# rf_smps.net
KiCad netlist of a schematic drawn in Altium Designer
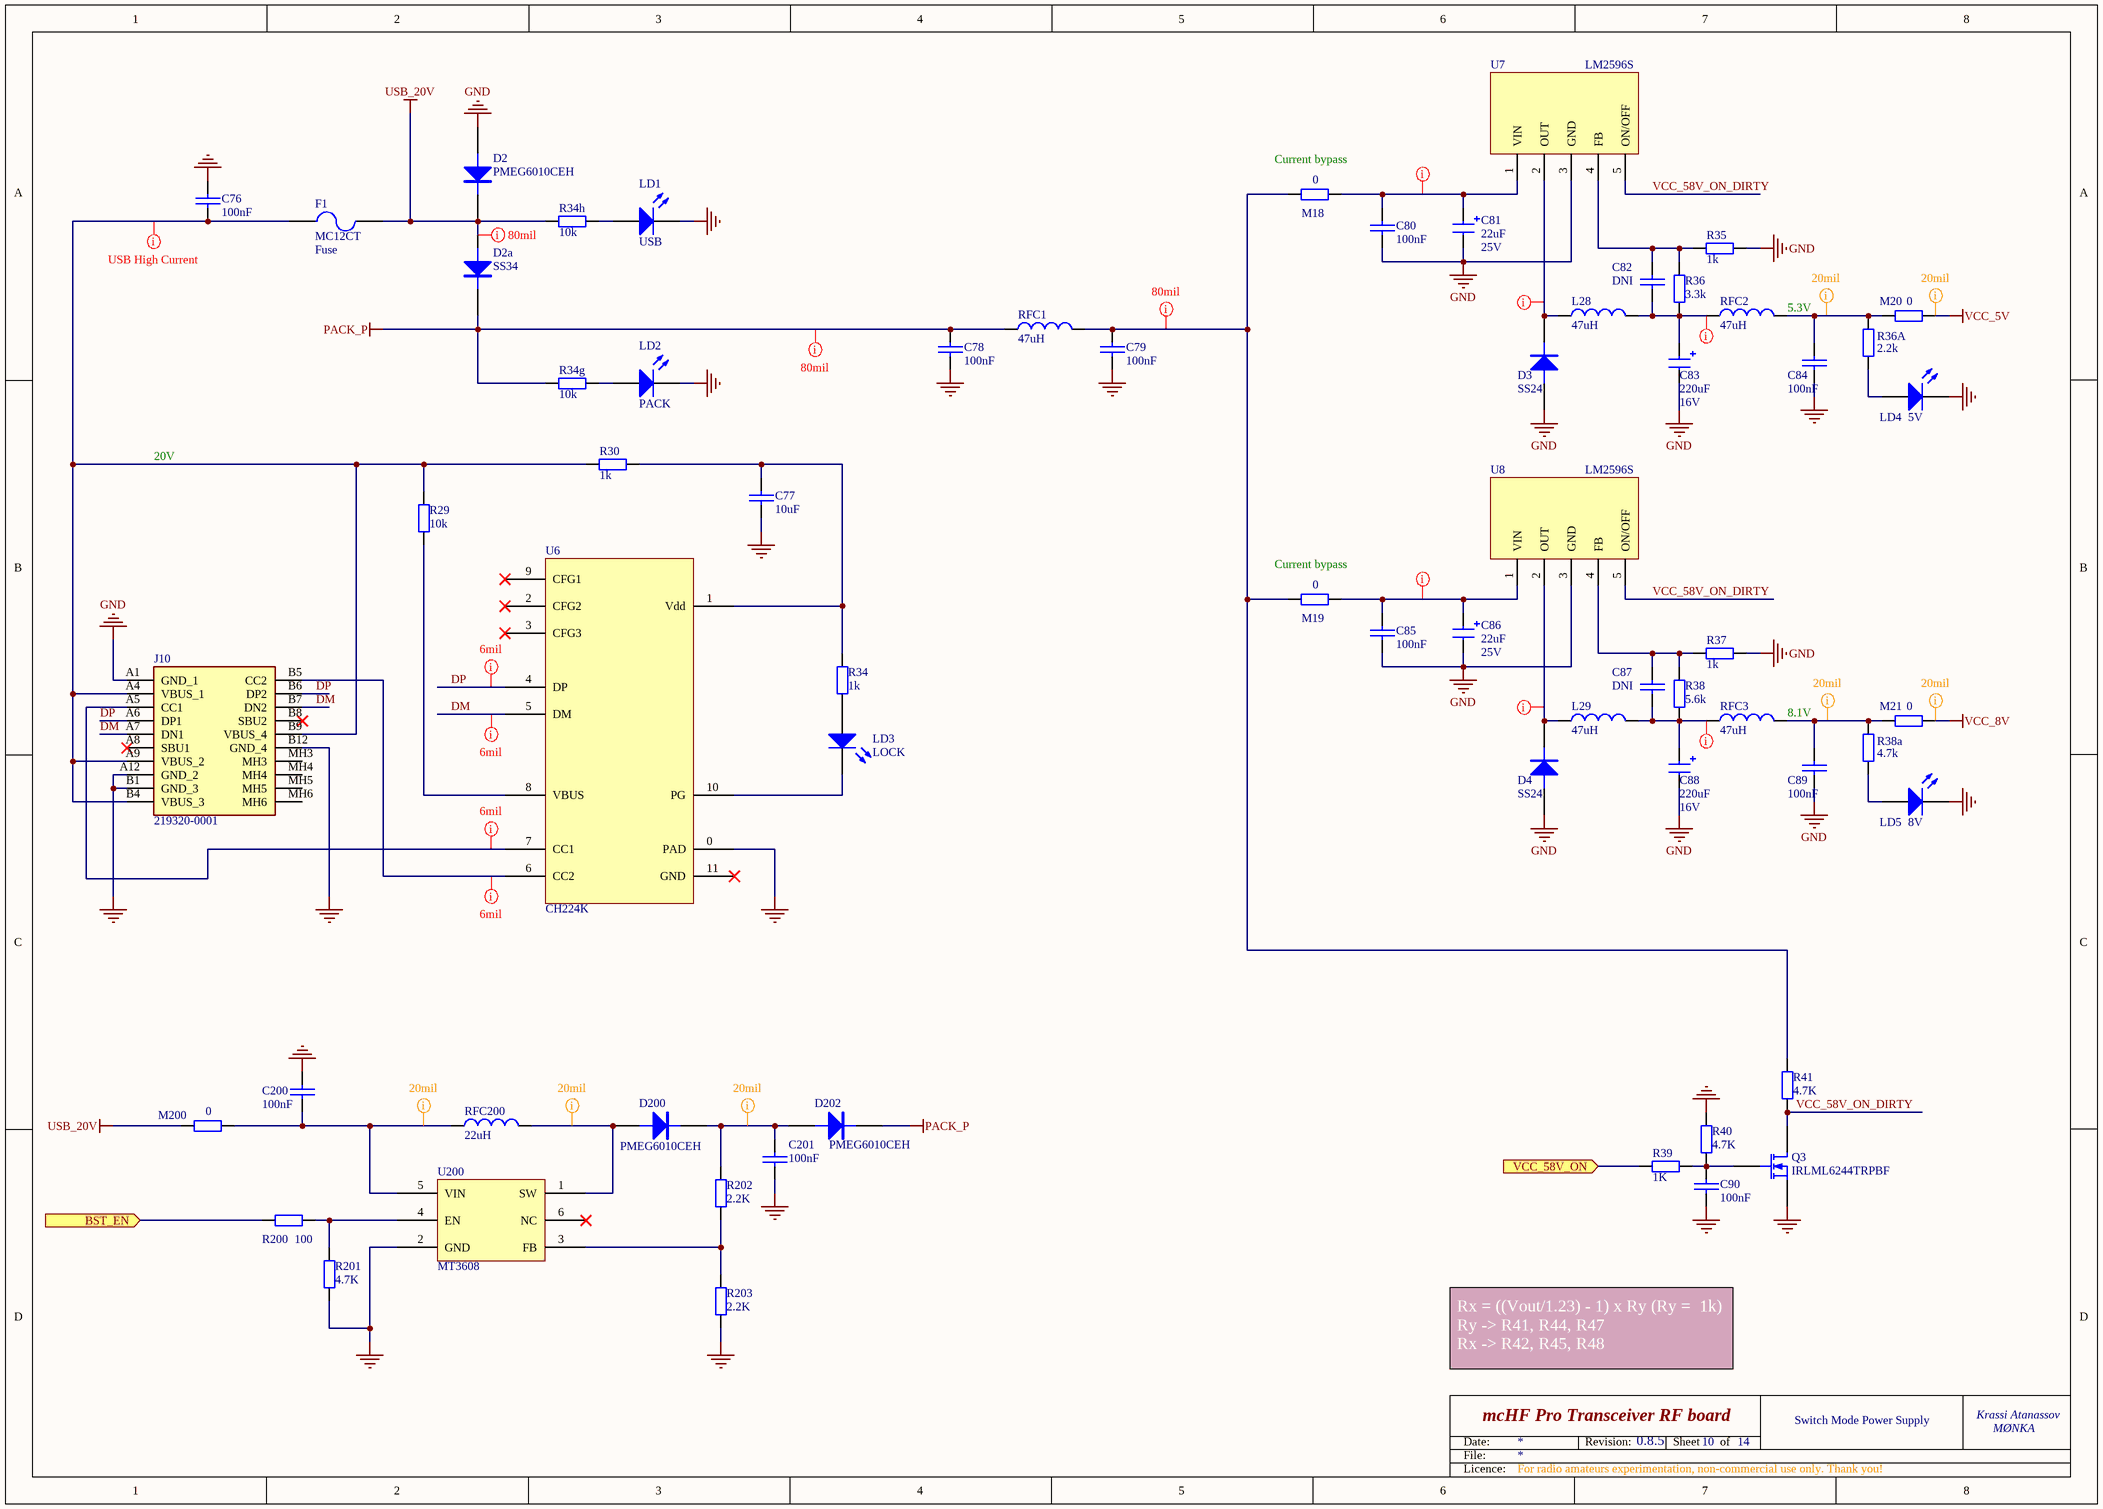
[diagram p0: rf_smps.SchDoc]

(export (version "E")
  (design (tool "Eeschema 10.0.6"))
  (components
    (comp (ref "C76")
      (value "100nF")
      (footprint "0805")
      (description "Capacitor")
      (libsource (lib "mcHF_rf") (part "CAP"))
    )
    (comp (ref "C77")
      (value "10uF")
      (footprint "0805")
      (description "Capacitor")
      (libsource (lib "mcHF_rf") (part "CAP"))
    )
    (comp (ref "C78")
      (value "100nF")
      (footprint "0805")
      (description "Capacitor")
      (fields (field (name "VOLTAGE") "100V"))
      (libsource (lib "mcHF_rf") (part "CAP"))
    )
    (comp (ref "C79")
      (value "100nF")
      (footprint "0805")
      (description "Capacitor")
      (fields (field (name "VOLTAGE") "100V"))
      (libsource (lib "mcHF_rf") (part "CAP"))
    )
    (comp (ref "C80")
      (value "100nF")
      (footprint "0805")
      (description "Capacitor")
      (fields (field (name "VOLTAGE") "100V"))
      (libsource (lib "mcHF_rf") (part "CAP"))
    )
    (comp (ref "C81")
      (value "22uF")
      (footprint "1206_Elec_Cap")
      (description "Electrolitic capacitor")
      (fields (field (name "VOLTAGE") "25V"))
      (libsource (lib "mcHF_rf") (part "CAP-POL"))
    )
    (comp (ref "C82")
      (value "DNI")
      (footprint "0805")
      (description "Capacitor")
      (fields (field (name "VOLTAGE") "100V"))
      (libsource (lib "mcHF_rf") (part "CAP"))
    )
    (comp (ref "C83")
      (value "220uF")
      (footprint "CAP_ALUM_Pro")
      (description "Electrolitic capacitor")
      (fields (field (name "VOLTAGE") "16V"))
      (libsource (lib "mcHF_rf") (part "CAP-POL"))
    )
    (comp (ref "C84")
      (value "100nF")
      (footprint "0805")
      (description "Capacitor")
      (fields (field (name "VOLTAGE") "100V"))
      (libsource (lib "mcHF_rf") (part "CAP"))
    )
    (comp (ref "C85")
      (value "100nF")
      (footprint "0805")
      (description "Capacitor")
      (fields (field (name "VOLTAGE") "100V"))
      (libsource (lib "mcHF_rf") (part "CAP"))
    )
    (comp (ref "C86")
      (value "22uF")
      (footprint "1206_Elec_Cap")
      (description "Electrolitic capacitor")
      (fields (field (name "VOLTAGE") "25V"))
      (libsource (lib "mcHF_rf") (part "CAP-POL"))
    )
    (comp (ref "C87")
      (value "DNI")
      (footprint "0805")
      (description "Capacitor")
      (fields (field (name "VOLTAGE") "100V"))
      (libsource (lib "mcHF_rf") (part "CAP"))
    )
    (comp (ref "C88")
      (value "220uF")
      (footprint "CAP_ALUM_Pro")
      (description "Electrolitic capacitor")
      (fields (field (name "VOLTAGE") "16V"))
      (libsource (lib "mcHF_rf") (part "CAP-POL"))
    )
    (comp (ref "C89")
      (value "100nF")
      (footprint "0805")
      (description "Capacitor")
      (fields (field (name "VOLTAGE") "100V"))
      (libsource (lib "mcHF_rf") (part "CAP"))
    )
    (comp (ref "C90")
      (value "100nF")
      (footprint "0805")
      (description "Capacitor")
      (fields (field (name "VOLTAGE") "100V"))
      (libsource (lib "mcHF_rf") (part "CAP"))
    )
    (comp (ref "C200")
      (value "100nF")
      (footprint "0805")
      (description "Capacitor")
      (libsource (lib "mcHF_ui") (part "CAP"))
    )
    (comp (ref "C201")
      (value "100nF")
      (footprint "0805")
      (description "Capacitor")
      (libsource (lib "mcHF_ui") (part "CAP"))
    )
    (comp (ref "D2")
      (value "PMEG6010CEH")
      (footprint "SOD87")
      (description "DIODE, SCHOTTKY, 1A, 60V, SOD-123F")
      (libsource (lib "mcHF_rf") (part "PMEG6010CEH"))
    )
    (comp (ref "D2a")
      (value "SS34")
      (footprint "DO214")
      (description "DIODE, SCHOTTKY, 1A, 60V, SOD-123F")
      (libsource (lib "mcHF_rf") (part "PMEG6010CEH"))
    )
    (comp (ref "D3")
      (value "SS24")
      (footprint "DO214")
      (description "DIODE, SCHOTTKY, 1A, 60V, SOD-123F")
      (libsource (lib "mcHF_rf") (part "PMEG6010CEH"))
    )
    (comp (ref "D4")
      (value "SS24")
      (footprint "DO214")
      (description "DIODE, SCHOTTKY, 1A, 60V, SOD-123F")
      (libsource (lib "mcHF_rf") (part "PMEG6010CEH"))
    )
    (comp (ref "D200")
      (value "PMEG6010CEH")
      (footprint "SOD87")
      (description "DIODE, SCHOTTKY, 1A, 60V, SOD-123F")
      (libsource (lib "mcHF_rf") (part "PMEG6010CEH"))
    )
    (comp (ref "D202")
      (value "PMEG6010CEH")
      (footprint "SOD87")
      (description "DIODE, SCHOTTKY, 1A, 60V, SOD-123F")
      (libsource (lib "mcHF_rf") (part "PMEG6010CEH"))
    )
    (comp (ref "F1")
      (value "MC12CT")
      (footprint "1206")
      (description "Fuse")
      (fields (field (name "FUNCTION") "Fuse"))
      (libsource (lib "mcHF_rf") (part "Fuse"))
    )
    (comp (ref "J10")
      (value "219320-0001")
      (footprint "MOLX_USB")
      (fields (field (name "MOUSER PART NUMBER") "538-219320-0001"))
      (libsource (lib "__rf") (part "219320-0001"))
    )
    (comp (ref "L28")
      (value "47uH")
      (footprint "CD75")
      (description "POWER INDUCTOR, 47UH, 1210")
      (libsource (lib "mcHF_rf") (part "TDK-NLV25T"))
    )
    (comp (ref "L29")
      (value "47uH")
      (footprint "CD75")
      (description "POWER INDUCTOR, 47UH, 1210")
      (libsource (lib "mcHF_rf") (part "TDK-NLV25T"))
    )
    (comp (ref "LD1")
      (value "USB")
      (footprint "1206_Elec_Cap")
      (description "LED 3mm")
      (libsource (lib "mcHF_ui") (part "LED2"))
    )
    (comp (ref "LD2")
      (value "PACK")
      (footprint "1206_Elec_Cap")
      (description "LED 3mm")
      (libsource (lib "mcHF_ui") (part "LED2"))
    )
    (comp (ref "LD3")
      (value "LOCK")
      (footprint "1206_Elec_Cap")
      (description "LED 3mm")
      (libsource (lib "mcHF_ui") (part "LED2"))
    )
    (comp (ref "LD4")
      (value "5V")
      (footprint "1206_Elec_Cap")
      (description "LED 3mm")
      (libsource (lib "mcHF_ui") (part "LED2"))
    )
    (comp (ref "LD5")
      (value "8V")
      (footprint "1206_Elec_Cap")
      (description "LED 3mm")
      (libsource (lib "mcHF_ui") (part "LED2"))
    )
    (comp (ref "M18")
      (value "0")
      (footprint "0805")
      (description "Resistor")
      (libsource (lib "") (part "RES_1"))
    )
    (comp (ref "M19")
      (value "0")
      (footprint "0805")
      (description "Resistor")
      (libsource (lib "") (part "RES_1"))
    )
    (comp (ref "M20")
      (value "0")
      (footprint "0805")
      (description "Resistor")
      (libsource (lib "") (part "RES_1"))
    )
    (comp (ref "M21")
      (value "0")
      (footprint "0805")
      (description "Resistor")
      (libsource (lib "") (part "RES_1"))
    )
    (comp (ref "M200")
      (value "0")
      (footprint "0805")
      (description "Resistor")
      (libsource (lib "") (part "RES_1"))
    )
    (comp (ref "Q3")
      (value "IRLML6244TRPBF")
      (footprint "SOT-23-Pro")
      (description "N-Channel MOSFET")
      (libsource (lib "mcHF_ui_b") (part "MOSFET-N"))
    )
    (comp (ref "R29")
      (value "10k")
      (footprint "0805")
      (description "Resistor")
      (libsource (lib "mcHF_rf") (part "RES"))
    )
    (comp (ref "R30")
      (value "1k")
      (footprint "0805")
      (description "Resistor")
      (libsource (lib "") (part "RES_2"))
    )
    (comp (ref "R34")
      (value "1k")
      (footprint "0805")
      (description "Resistor")
      (libsource (lib "mcHF_rf") (part "RES"))
    )
    (comp (ref "R34g")
      (value "10k")
      (footprint "0805")
      (description "Resistor")
      (libsource (lib "") (part "RES_1"))
    )
    (comp (ref "R34h")
      (value "10k")
      (footprint "0805")
      (description "Resistor")
      (libsource (lib "") (part "RES_1"))
    )
    (comp (ref "R35")
      (value "1k")
      (footprint "0805")
      (description "Resistor")
      (libsource (lib "") (part "RES_2"))
    )
    (comp (ref "R36")
      (value "3.3k")
      (footprint "0805")
      (description "Resistor")
      (libsource (lib "mcHF_rf") (part "RES"))
    )
    (comp (ref "R36A")
      (value "2.2k")
      (footprint "0805")
      (description "Resistor")
      (libsource (lib "mcHF_rf") (part "RES"))
    )
    (comp (ref "R37")
      (value "1k")
      (footprint "0805")
      (description "Resistor")
      (libsource (lib "") (part "RES_2"))
    )
    (comp (ref "R38")
      (value "5.6k")
      (footprint "0805")
      (description "Resistor")
      (libsource (lib "mcHF_rf") (part "RES"))
    )
    (comp (ref "R38a")
      (value "4.7k")
      (footprint "0805")
      (description "Resistor")
      (libsource (lib "mcHF_rf") (part "RES"))
    )
    (comp (ref "R39")
      (value "1K")
      (footprint "0805")
      (description "Resistor")
      (libsource (lib "") (part "RES_2"))
    )
    (comp (ref "R40")
      (value "4.7K")
      (footprint "0805")
      (description "Resistor")
      (libsource (lib "mcHF_rf") (part "RES"))
    )
    (comp (ref "R41")
      (value "4.7K")
      (footprint "0805")
      (description "Resistor")
      (libsource (lib "mcHF_rf") (part "RES"))
    )
    (comp (ref "R200")
      (value "100")
      (footprint "0805")
      (description "Resistor")
      (libsource (lib "") (part "RES_2"))
    )
    (comp (ref "R201")
      (value "4.7K")
      (footprint "0805")
      (description "Resistor")
      (libsource (lib "") (part "RES_1"))
    )
    (comp (ref "R202")
      (value "2.2K")
      (footprint "0805")
      (description "Resistor")
      (libsource (lib "mcHF_ui") (part "RES"))
    )
    (comp (ref "R203")
      (value "2.2K")
      (footprint "0805")
      (description "Resistor")
      (libsource (lib "mcHF_ui") (part "RES"))
    )
    (comp (ref "RFC1")
      (value "47uH")
      (footprint "BIG_IND")
      (description "POWER INDUCTOR, 47UH, 1210")
      (libsource (lib "mcHF_rf") (part "TDK-NLV25T"))
    )
    (comp (ref "RFC2")
      (value "47uH")
      (footprint "CD75")
      (description "POWER INDUCTOR, 47UH, 1210")
      (libsource (lib "mcHF_rf") (part "TDK-NLV25T"))
    )
    (comp (ref "RFC3")
      (value "47uH")
      (footprint "CD75")
      (description "POWER INDUCTOR, 47UH, 1210")
      (libsource (lib "mcHF_rf") (part "TDK-NLV25T"))
    )
    (comp (ref "RFC200")
      (value "22uH")
      (footprint "0805")
      (description "Power Inductor")
      (libsource (lib "mcHF_ui") (part "Inductor"))
    )
    (comp (ref "U6")
      (value "CH224K")
      (footprint "ch224k")
      (description "USB-PD trigger chip")
      (libsource (lib "__rf") (part "CH224K"))
    )
    (comp (ref "U7")
      (value "LM2596S")
      (footprint "TO-263-5")
      (description "V REG ADJ +5/20V, SMPS TO-263-5")
      (libsource (lib "mcHF_rf") (part "LM2596S"))
    )
    (comp (ref "U8")
      (value "LM2596S")
      (footprint "TO-263-5")
      (description "V REG ADJ +5/20V, SMPS TO-263-5")
      (libsource (lib "mcHF_rf") (part "LM2596S"))
    )
    (comp (ref "U200")
      (value "MT3608")
      (footprint "SOT25-6")
      (description "Charge Pump")
      (libsource (lib "__rf") (part "MT3608"))
    )
  )
  (nets
    (net (code "1") (name "/BST_EN") (class "Default")
      (node (ref "R200") (pin "1") (pinfunction "1_1") (pintype "passive"))
    )
    (net (code "2") (name "/DM") (class "Default")
      (node (ref "J10") (pin "A7") (pinfunction "DN1_A7") (pintype "passive"))
      (node (ref "J10") (pin "B7") (pinfunction "DN2_B7") (pintype "passive"))
      (node (ref "U6") (pin "5") (pinfunction "DM_5") (pintype "passive"))
    )
    (net (code "3") (name "/DP") (class "Default")
      (node (ref "J10") (pin "A6") (pinfunction "DP1_A6") (pintype "passive"))
      (node (ref "J10") (pin "B6") (pinfunction "DP2_B6") (pintype "passive"))
      (node (ref "U6") (pin "4") (pinfunction "DP_4") (pintype "passive"))
    )
    (net (code "4") (name "/VCC_58V_ON") (class "Default")
      (node (ref "R39") (pin "1") (pinfunction "1_1") (pintype "passive"))
    )
    (net (code "5") (name "/VCC_58V_ON_DIRTY") (class "Default")
      (node (ref "Q3") (pin "3") (pinfunction "D_3") (pintype "passive"))
      (node (ref "R41") (pin "1") (pinfunction "1_1") (pintype "passive"))
      (node (ref "U7") (pin "5") (pinfunction "ON/OFF_5") (pintype "passive"))
      (node (ref "U8") (pin "5") (pinfunction "ON/OFF_5") (pintype "passive"))
    )
    (net (code "6") (name "GND") (class "Default")
      (node (ref "C200") (pin "1") (pinfunction "1_1") (pintype "passive"))
      (node (ref "C201") (pin "2") (pinfunction "2_2") (pintype "passive"))
      (node (ref "C76") (pin "1") (pinfunction "1_1") (pintype "passive"))
      (node (ref "C77") (pin "2") (pinfunction "2_2") (pintype "passive"))
      (node (ref "C78") (pin "1") (pinfunction "1_1") (pintype "passive"))
      (node (ref "C79") (pin "1") (pinfunction "1_1") (pintype "passive"))
      (node (ref "C80") (pin "2") (pinfunction "2_2") (pintype "passive"))
      (node (ref "C81") (pin "2") (pinfunction "2_2") (pintype "passive"))
      (node (ref "C83") (pin "2") (pinfunction "2_2") (pintype "passive"))
      (node (ref "C84") (pin "2") (pinfunction "2_2") (pintype "passive"))
      (node (ref "C85") (pin "2") (pinfunction "2_2") (pintype "passive"))
      (node (ref "C86") (pin "2") (pinfunction "2_2") (pintype "passive"))
      (node (ref "C88") (pin "2") (pinfunction "2_2") (pintype "passive"))
      (node (ref "C89") (pin "2") (pinfunction "2_2") (pintype "passive"))
      (node (ref "C90") (pin "2") (pinfunction "2_2") (pintype "passive"))
      (node (ref "D2") (pin "1") (pinfunction "A_1") (pintype "passive"))
      (node (ref "D3") (pin "1") (pinfunction "A_1") (pintype "passive"))
      (node (ref "D4") (pin "1") (pinfunction "A_1") (pintype "passive"))
      (node (ref "J10") (pin "A1") (pinfunction "GND_1_A1") (pintype "passive"))
      (node (ref "J10") (pin "A12") (pinfunction "GND_2_A12") (pintype "passive"))
      (node (ref "J10") (pin "B1") (pinfunction "GND_3_B1") (pintype "passive"))
      (node (ref "J10") (pin "B12") (pinfunction "GND_4_B12") (pintype "passive"))
      (node (ref "LD1") (pin "2") (pinfunction "K_2") (pintype "passive"))
      (node (ref "LD2") (pin "2") (pinfunction "K_2") (pintype "passive"))
      (node (ref "LD4") (pin "2") (pinfunction "K_2") (pintype "passive"))
      (node (ref "LD5") (pin "2") (pinfunction "K_2") (pintype "passive"))
      (node (ref "Q3") (pin "2") (pinfunction "S_2") (pintype "passive"))
      (node (ref "R201") (pin "1") (pinfunction "1_1") (pintype "passive"))
      (node (ref "R203") (pin "2") (pinfunction "2_2") (pintype "passive"))
      (node (ref "R35") (pin "2") (pinfunction "2_2") (pintype "passive"))
      (node (ref "R37") (pin "2") (pinfunction "2_2") (pintype "passive"))
      (node (ref "R40") (pin "2") (pinfunction "2_2") (pintype "passive"))
      (node (ref "U200") (pin "2") (pinfunction "GND_2") (pintype "passive"))
      (node (ref "U6") (pin "0") (pinfunction "PAD_0") (pintype "power_in"))
      (node (ref "U7") (pin "3") (pinfunction "GND_3") (pintype "passive"))
      (node (ref "U8") (pin "3") (pinfunction "GND_3") (pintype "passive"))
    )
    (net (code "7") (name "Net-(C79-Pad2)") (class "Default")
      (node (ref "C79") (pin "2") (pinfunction "2_2") (pintype "passive"))
      (node (ref "M18") (pin "2") (pinfunction "2_2") (pintype "passive"))
      (node (ref "M19") (pin "2") (pinfunction "2_2") (pintype "passive"))
      (node (ref "R41") (pin "2") (pinfunction "2_2") (pintype "passive"))
      (node (ref "RFC1") (pin "2") (pinfunction "2_2") (pintype "passive"))
    )
    (net (code "8") (name "Net-(C82-Pad2)") (class "Default")
      (node (ref "C82") (pin "2") (pinfunction "2_2") (pintype "passive"))
      (node (ref "C83") (pin "1") (pinfunction "1_1") (pintype "passive"))
      (node (ref "L28") (pin "2") (pinfunction "2_2") (pintype "passive"))
      (node (ref "R36") (pin "1") (pinfunction "1_1") (pintype "passive"))
      (node (ref "RFC2") (pin "1") (pinfunction "1_1") (pintype "passive"))
    )
    (net (code "9") (name "Net-(C84-Pad1)") (class "Default")
      (node (ref "C84") (pin "1") (pinfunction "1_1") (pintype "passive"))
      (node (ref "M20") (pin "2") (pinfunction "2_2") (pintype "passive"))
      (node (ref "R36A") (pin "2") (pinfunction "2_2") (pintype "passive"))
      (node (ref "RFC2") (pin "2") (pinfunction "2_2") (pintype "passive"))
    )
    (net (code "10") (name "Net-(C87-Pad2)") (class "Default")
      (node (ref "C87") (pin "2") (pinfunction "2_2") (pintype "passive"))
      (node (ref "C88") (pin "1") (pinfunction "1_1") (pintype "passive"))
      (node (ref "L29") (pin "2") (pinfunction "2_2") (pintype "passive"))
      (node (ref "R38") (pin "1") (pinfunction "1_1") (pintype "passive"))
      (node (ref "RFC3") (pin "1") (pinfunction "1_1") (pintype "passive"))
    )
    (net (code "11") (name "Net-(C89-Pad1)") (class "Default")
      (node (ref "C89") (pin "1") (pinfunction "1_1") (pintype "passive"))
      (node (ref "M21") (pin "2") (pinfunction "2_2") (pintype "passive"))
      (node (ref "R38a") (pin "2") (pinfunction "2_2") (pintype "passive"))
      (node (ref "RFC3") (pin "2") (pinfunction "2_2") (pintype "passive"))
    )
    (net (code "12") (name "Net-(D3-K)") (class "Default")
      (node (ref "D3") (pin "2") (pinfunction "K_2") (pintype "passive"))
      (node (ref "L28") (pin "1") (pinfunction "1_1") (pintype "passive"))
      (node (ref "U7") (pin "2") (pinfunction "OUT_2") (pintype "passive"))
    )
    (net (code "13") (name "Net-(D4-K)") (class "Default")
      (node (ref "D4") (pin "2") (pinfunction "K_2") (pintype "passive"))
      (node (ref "L29") (pin "1") (pinfunction "1_1") (pintype "passive"))
      (node (ref "U8") (pin "2") (pinfunction "OUT_2") (pintype "passive"))
    )
    (net (code "14") (name "Net-(D200-A)") (class "Default")
      (node (ref "D200") (pin "1") (pinfunction "A_1") (pintype "passive"))
      (node (ref "RFC200") (pin "2") (pinfunction "2_2") (pintype "passive"))
      (node (ref "U200") (pin "1") (pinfunction "SW_1") (pintype "passive"))
    )
    (net (code "15") (name "Net-(D200-K)") (class "Default")
      (node (ref "C201") (pin "1") (pinfunction "1_1") (pintype "passive"))
      (node (ref "D200") (pin "2") (pinfunction "K_2") (pintype "passive"))
      (node (ref "D202") (pin "1") (pinfunction "A_1") (pintype "passive"))
      (node (ref "R202") (pin "1") (pinfunction "1_1") (pintype "passive"))
    )
    (net (code "16") (name "Net-(J10-CC1)") (class "Default")
      (node (ref "J10") (pin "A5") (pinfunction "CC1_A5") (pintype "passive"))
      (node (ref "U6") (pin "7") (pinfunction "CC1_7") (pintype "passive"))
    )
    (net (code "17") (name "Net-(J10-CC2)") (class "Default")
      (node (ref "J10") (pin "B5") (pinfunction "CC2_B5") (pintype "passive"))
      (node (ref "U6") (pin "6") (pinfunction "CC2_6") (pintype "passive"))
    )
    (net (code "18") (name "Net-(J10-VBUS_1)") (class "Default")
      (node (ref "C76") (pin "2") (pinfunction "2_2") (pintype "passive"))
      (node (ref "F1") (pin "2") (pinfunction "2_2") (pintype "passive"))
      (node (ref "J10") (pin "A4") (pinfunction "VBUS_1_A4") (pintype "passive"))
      (node (ref "J10") (pin "A9") (pinfunction "VBUS_2_A9") (pintype "passive"))
      (node (ref "J10") (pin "B4") (pinfunction "VBUS_3_B4") (pintype "passive"))
      (node (ref "J10") (pin "B9") (pinfunction "VBUS_4_B9") (pintype "passive"))
      (node (ref "R29") (pin "2") (pinfunction "2_2") (pintype "passive"))
      (node (ref "R30") (pin "1") (pinfunction "1_1") (pintype "passive"))
    )
    (net (code "19") (name "Net-(LD1-A)") (class "Default")
      (node (ref "LD1") (pin "1") (pinfunction "A_1") (pintype "passive"))
      (node (ref "R34h") (pin "1") (pinfunction "1_1") (pintype "passive"))
    )
    (net (code "20") (name "Net-(LD2-A)") (class "Default")
      (node (ref "LD2") (pin "1") (pinfunction "A_1") (pintype "passive"))
      (node (ref "R34g") (pin "1") (pinfunction "1_1") (pintype "passive"))
    )
    (net (code "21") (name "Net-(LD3-A)") (class "Default")
      (node (ref "LD3") (pin "1") (pinfunction "A_1") (pintype "passive"))
      (node (ref "R34") (pin "1") (pinfunction "1_1") (pintype "passive"))
    )
    (net (code "22") (name "Net-(LD3-K)") (class "Default")
      (node (ref "LD3") (pin "2") (pinfunction "K_2") (pintype "passive"))
      (node (ref "U6") (pin "10") (pinfunction "PG_10") (pintype "passive"))
    )
    (net (code "23") (name "Net-(LD4-A)") (class "Default")
      (node (ref "LD4") (pin "1") (pinfunction "A_1") (pintype "passive"))
      (node (ref "R36A") (pin "1") (pinfunction "1_1") (pintype "passive"))
    )
    (net (code "24") (name "Net-(LD5-A)") (class "Default")
      (node (ref "LD5") (pin "1") (pinfunction "A_1") (pintype "passive"))
      (node (ref "R38a") (pin "1") (pinfunction "1_1") (pintype "passive"))
    )
    (net (code "25") (name "Net-(Q3-G)") (class "Default")
      (node (ref "C90") (pin "1") (pinfunction "1_1") (pintype "passive"))
      (node (ref "Q3") (pin "1") (pinfunction "G_1") (pintype "passive"))
      (node (ref "R39") (pin "2") (pinfunction "2_2") (pintype "passive"))
      (node (ref "R40") (pin "1") (pinfunction "1_1") (pintype "passive"))
    )
    (net (code "26") (name "Net-(U6-VBUS)") (class "Default")
      (node (ref "R29") (pin "1") (pinfunction "1_1") (pintype "passive"))
      (node (ref "U6") (pin "8") (pinfunction "VBUS_8") (pintype "power_in"))
    )
    (net (code "27") (name "Net-(U6-Vdd)") (class "Default")
      (node (ref "C77") (pin "1") (pinfunction "1_1") (pintype "passive"))
      (node (ref "R30") (pin "2") (pinfunction "2_2") (pintype "passive"))
      (node (ref "R34") (pin "2") (pinfunction "2_2") (pintype "passive"))
      (node (ref "U6") (pin "1") (pinfunction "Vdd_1") (pintype "power_in"))
    )
    (net (code "28") (name "Net-(U7-FB)") (class "Default")
      (node (ref "C82") (pin "1") (pinfunction "1_1") (pintype "passive"))
      (node (ref "R35") (pin "1") (pinfunction "1_1") (pintype "passive"))
      (node (ref "R36") (pin "2") (pinfunction "2_2") (pintype "passive"))
      (node (ref "U7") (pin "4") (pinfunction "FB_4") (pintype "passive"))
    )
    (net (code "29") (name "Net-(U7-VIN)") (class "Default")
      (node (ref "C80") (pin "1") (pinfunction "1_1") (pintype "passive"))
      (node (ref "C81") (pin "1") (pinfunction "1_1") (pintype "passive"))
      (node (ref "M18") (pin "1") (pinfunction "1_1") (pintype "passive"))
      (node (ref "U7") (pin "1") (pinfunction "VIN_1") (pintype "passive"))
    )
    (net (code "30") (name "Net-(U8-FB)") (class "Default")
      (node (ref "C87") (pin "1") (pinfunction "1_1") (pintype "passive"))
      (node (ref "R37") (pin "1") (pinfunction "1_1") (pintype "passive"))
      (node (ref "R38") (pin "2") (pinfunction "2_2") (pintype "passive"))
      (node (ref "U8") (pin "4") (pinfunction "FB_4") (pintype "passive"))
    )
    (net (code "31") (name "Net-(U8-VIN)") (class "Default")
      (node (ref "C85") (pin "1") (pinfunction "1_1") (pintype "passive"))
      (node (ref "C86") (pin "1") (pinfunction "1_1") (pintype "passive"))
      (node (ref "M19") (pin "1") (pinfunction "1_1") (pintype "passive"))
      (node (ref "U8") (pin "1") (pinfunction "VIN_1") (pintype "passive"))
    )
    (net (code "32") (name "Net-(U200-EN)") (class "Default")
      (node (ref "R200") (pin "2") (pinfunction "2_2") (pintype "passive"))
      (node (ref "R201") (pin "2") (pinfunction "2_2") (pintype "passive"))
      (node (ref "U200") (pin "4") (pinfunction "EN_4") (pintype "passive"))
    )
    (net (code "33") (name "Net-(U200-FB)") (class "Default")
      (node (ref "R202") (pin "2") (pinfunction "2_2") (pintype "passive"))
      (node (ref "R203") (pin "1") (pinfunction "1_1") (pintype "passive"))
      (node (ref "U200") (pin "3") (pinfunction "FB_3") (pintype "passive"))
    )
    (net (code "34") (name "Net-(U200-VIN)") (class "Default")
      (node (ref "C200") (pin "2") (pinfunction "2_2") (pintype "passive"))
      (node (ref "M200") (pin "1") (pinfunction "1_1") (pintype "passive"))
      (node (ref "RFC200") (pin "1") (pinfunction "1_1") (pintype "passive"))
      (node (ref "U200") (pin "5") (pinfunction "VIN_5") (pintype "passive"))
    )
    (net (code "35") (name "PACK_P") (class "Default")
      (node (ref "C78") (pin "2") (pinfunction "2_2") (pintype "passive"))
      (node (ref "D202") (pin "2") (pinfunction "K_2") (pintype "passive"))
      (node (ref "D2a") (pin "2") (pinfunction "K_2") (pintype "passive"))
      (node (ref "R34g") (pin "2") (pinfunction "2_2") (pintype "passive"))
      (node (ref "RFC1") (pin "1") (pinfunction "1_1") (pintype "passive"))
    )
    (net (code "36") (name "USB_20V") (class "Default")
      (node (ref "D2") (pin "2") (pinfunction "K_2") (pintype "passive"))
      (node (ref "D2a") (pin "1") (pinfunction "A_1") (pintype "passive"))
      (node (ref "F1") (pin "1") (pinfunction "1_1") (pintype "passive"))
      (node (ref "M200") (pin "2") (pinfunction "2_2") (pintype "passive"))
      (node (ref "R34h") (pin "2") (pinfunction "2_2") (pintype "passive"))
    )
    (net (code "37") (name "VCC_5V") (class "Default")
      (node (ref "M20") (pin "1") (pinfunction "1_1") (pintype "passive"))
    )
    (net (code "38") (name "VCC_8V") (class "Default")
      (node (ref "M21") (pin "1") (pinfunction "1_1") (pintype "passive"))
    )
    (net (code "39") (name "unconnected-(J10-PadMH3)") (class "Default")
      (node (ref "J10") (pin "MH3") (pinfunction "MH3_MH3") (pintype "passive"))
    )
    (net (code "40") (name "unconnected-(J10-PadMH4)") (class "Default")
      (node (ref "J10") (pin "MH4") (pinfunction "MH4_MH4") (pintype "passive"))
    )
    (net (code "41") (name "unconnected-(J10-PadMH5)") (class "Default")
      (node (ref "J10") (pin "MH5") (pinfunction "MH5_MH5") (pintype "passive"))
    )
    (net (code "42") (name "unconnected-(J10-PadMH6)") (class "Default")
      (node (ref "J10") (pin "MH6") (pinfunction "MH6_MH6") (pintype "passive"))
    )
    (net (code "43") (name "unconnected-(J10-SBU1-PadA8)") (class "Default")
      (node (ref "J10") (pin "A8") (pinfunction "SBU1_A8") (pintype "passive+no_connect"))
    )
    (net (code "44") (name "unconnected-(J10-SBU2-PadB8)") (class "Default")
      (node (ref "J10") (pin "B8") (pinfunction "SBU2_B8") (pintype "passive+no_connect"))
    )
    (net (code "45") (name "unconnected-(U6-CFG1-Pad9)") (class "Default")
      (node (ref "U6") (pin "9") (pinfunction "CFG1_9") (pintype "passive+no_connect"))
    )
    (net (code "46") (name "unconnected-(U6-CFG2-Pad2)") (class "Default")
      (node (ref "U6") (pin "2") (pinfunction "CFG2_2") (pintype "passive+no_connect"))
    )
    (net (code "47") (name "unconnected-(U6-CFG3-Pad3)") (class "Default")
      (node (ref "U6") (pin "3") (pinfunction "CFG3_3") (pintype "passive+no_connect"))
    )
    (net (code "48") (name "unconnected-(U6-GND-Pad11)") (class "Default")
      (node (ref "U6") (pin "11") (pinfunction "GND_11") (pintype "power_in+no_connect"))
    )
    (net (code "49") (name "unconnected-(U200-NC-Pad6)") (class "Default")
      (node (ref "U200") (pin "6") (pinfunction "NC_6") (pintype "passive+no_connect"))
    )
  )
)
